# 328p_DIP_Galv_009_gnd.net
KiCad netlist of a schematic drawn in EAGLE
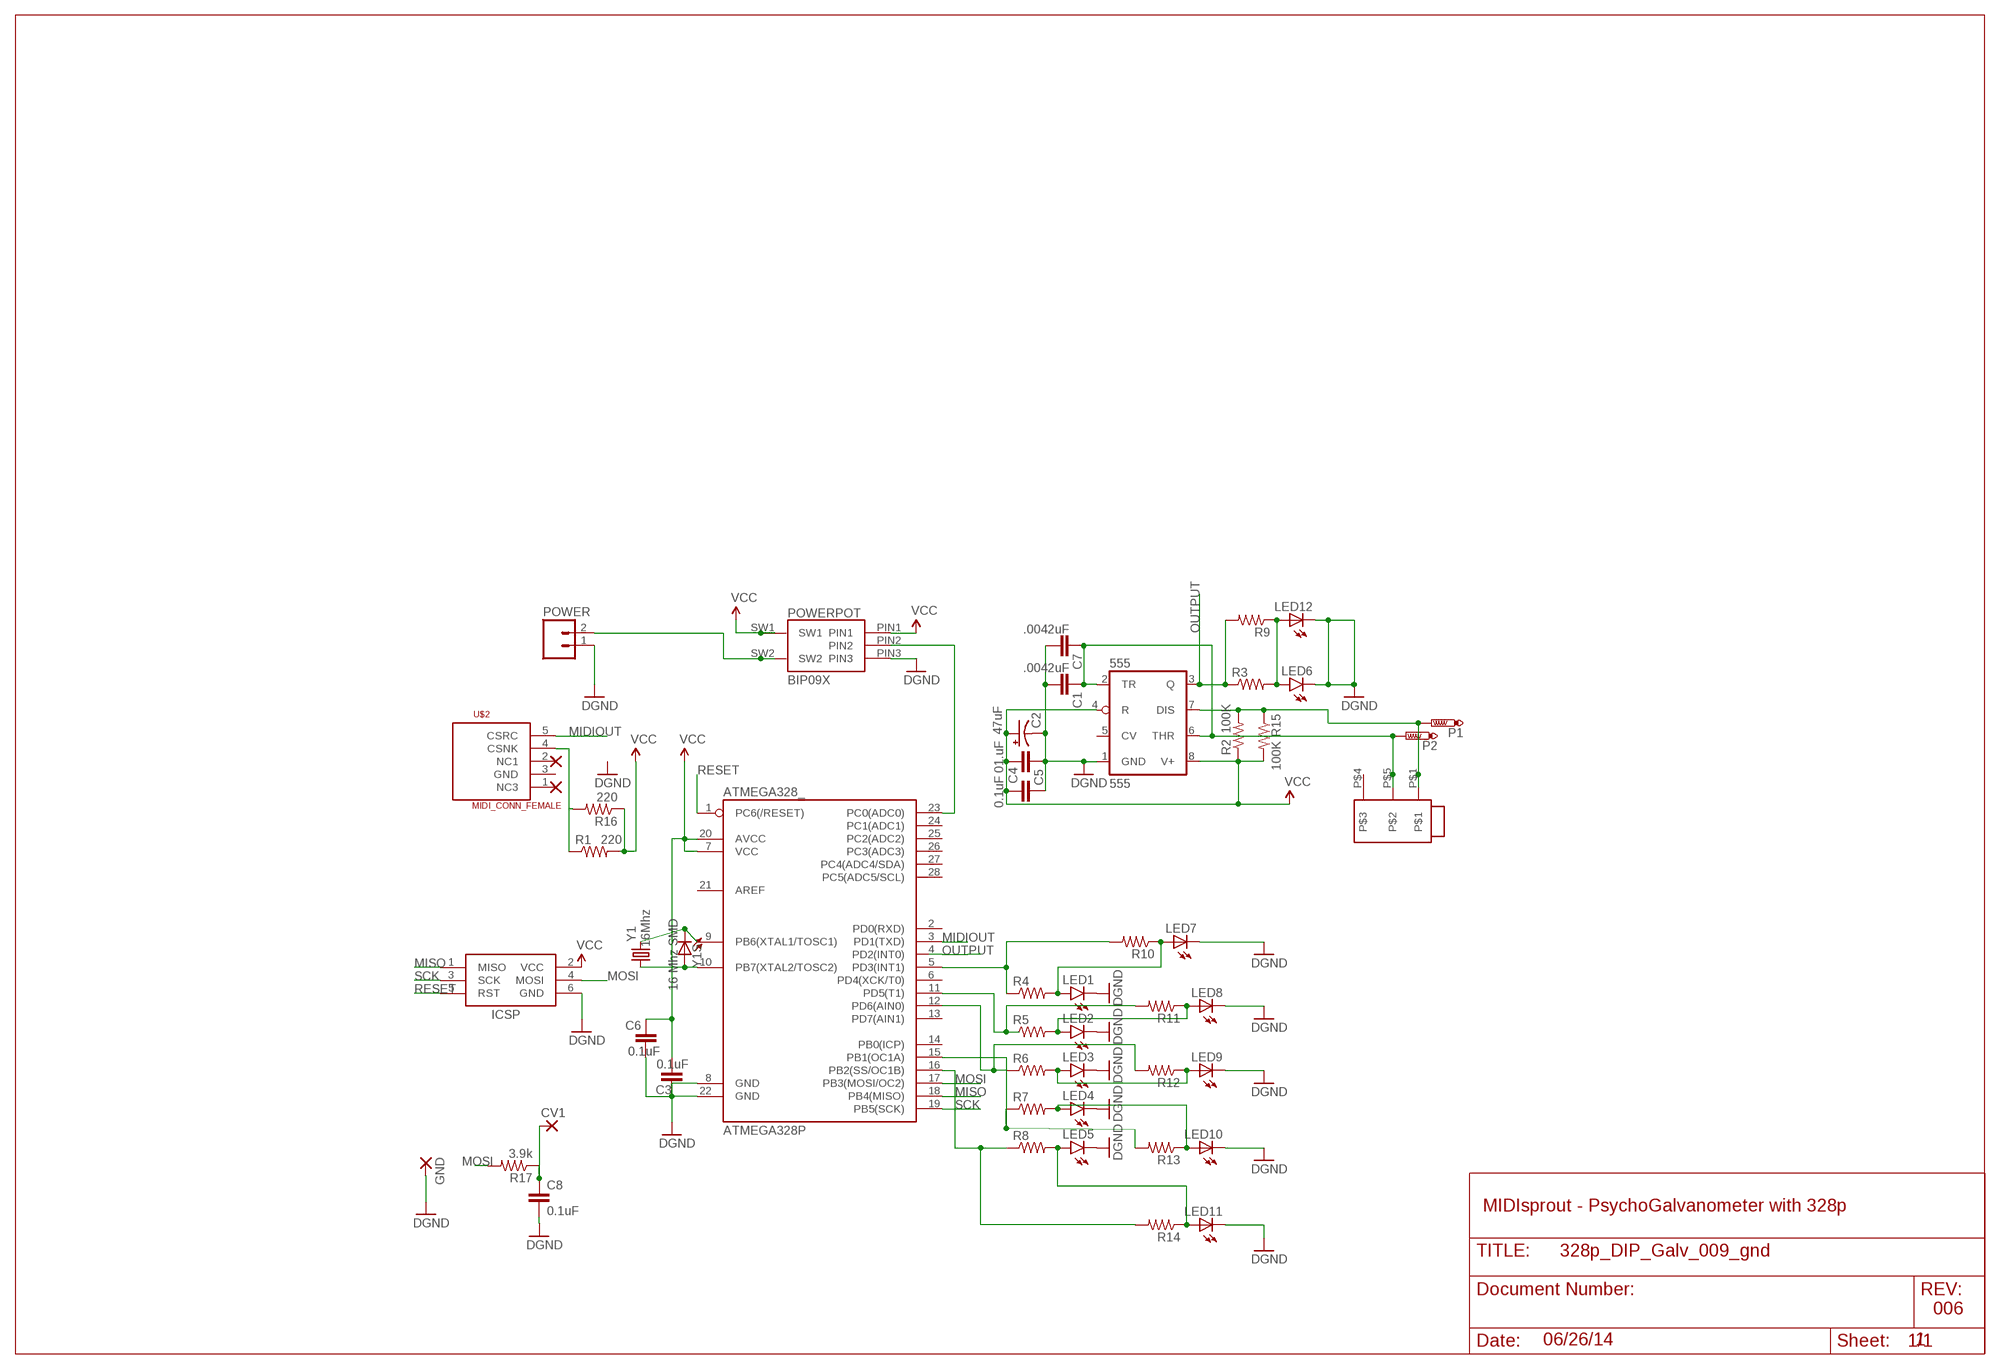
[diagram p0: schematic, sheet 1]

(export (version "E")
  (design (tool "Eeschema 10.0.6"))
  (components
    (comp (ref "555")
      (value "555")
      (footprint "eagle-import:DIL08-ROUND")
      (libsource (lib "eagle-import") (part "555NLM"))
    )
    (comp (ref "ATMEGA328_")
      (value "ATMEGA328P")
      (footprint "eagle-import:DIL28-3")
      (libsource (lib "eagle-import") (part "ATMEGA328P_PDIP"))
    )
    (comp (ref "C1")
      (value ".0042uF")
      (footprint "eagle-import:CAP-PTH-SMALL")
      (libsource (lib "eagle-import") (part "SparkFun-Passives_CAPPTH"))
    )
    (comp (ref "C2")
      (value "47uF")
      (footprint "eagle-import:CPOL-RADIAL-10UF-25V")
      (libsource (lib "eagle-import") (part "CAP_POLPTH2"))
    )
    (comp (ref "C3")
      (value "0.1uF")
      (footprint "eagle-import:CAP-PTH-SMALL")
      (libsource (lib "eagle-import") (part "CAPPTH"))
    )
    (comp (ref "C4")
      (value "0.1uF")
      (footprint "eagle-import:CAP-PTH-SMALL")
      (libsource (lib "eagle-import") (part "CAPPTH"))
    )
    (comp (ref "C5")
      (value "01.uF")
      (footprint "eagle-import:1206")
      (libsource (lib "eagle-import") (part "SparkFun-Passives_CAP1206"))
    )
    (comp (ref "C6")
      (value "0.1uF")
      (footprint "eagle-import:1206")
      (libsource (lib "eagle-import") (part "SparkFun-Passives_CAP1206"))
    )
    (comp (ref "C7")
      (value ".0042uF")
      (footprint "eagle-import:1206")
      (libsource (lib "eagle-import") (part "SparkFun-Passives_CAP1206"))
    )
    (comp (ref "C8")
      (value "0.1uF")
      (footprint "eagle-import:1206")
      (libsource (lib "eagle-import") (part "SparkFun-Passives_CAP1206"))
    )
    (comp (ref "CV1")
      (value "2,54/1,1")
      (footprint "eagle-import:2,54_1,1")
      (libsource (lib "eagle-import") (part "2,54/1,1"))
    )
    (comp (ref "GND")
      (value "2,54/1,1")
      (footprint "eagle-import:2,54_1,1")
      (libsource (lib "eagle-import") (part "2,54/1,1"))
    )
    (comp (ref "ICSP")
      (value "AVRISP-6")
      (footprint "eagle-import:AVRISP")
      (libsource (lib "eagle-import") (part "AVRISP-6"))
    )
    (comp (ref "LED1")
      (value "LED5MM")
      (footprint "eagle-import:LED5MM")
      (libsource (lib "eagle-import") (part "LED5MM"))
    )
    (comp (ref "LED2")
      (value "LED5MM")
      (footprint "eagle-import:LED5MM")
      (libsource (lib "eagle-import") (part "LED5MM"))
    )
    (comp (ref "LED3")
      (value "LED5MM")
      (footprint "eagle-import:LED5MM")
      (libsource (lib "eagle-import") (part "LED5MM"))
    )
    (comp (ref "LED4")
      (value "LED5MM")
      (footprint "eagle-import:LED5MM")
      (libsource (lib "eagle-import") (part "LED5MM"))
    )
    (comp (ref "LED5")
      (value "LED5MM")
      (footprint "eagle-import:LED5MM")
      (libsource (lib "eagle-import") (part "LED5MM"))
    )
    (comp (ref "LED6")
      (value "LED5MM")
      (footprint "eagle-import:LED5MM")
      (libsource (lib "eagle-import") (part "LED5MM"))
    )
    (comp (ref "LED7")
      (value "LEDSML1206")
      (footprint "eagle-import:SML1206")
      (libsource (lib "eagle-import") (part "LEDSML1206"))
    )
    (comp (ref "LED8")
      (value "LEDSML1206")
      (footprint "eagle-import:SML1206")
      (libsource (lib "eagle-import") (part "LEDSML1206"))
    )
    (comp (ref "LED9")
      (value "LEDSML1206")
      (footprint "eagle-import:SML1206")
      (libsource (lib "eagle-import") (part "LEDSML1206"))
    )
    (comp (ref "LED10")
      (value "LEDSML1206")
      (footprint "eagle-import:SML1206")
      (libsource (lib "eagle-import") (part "LEDSML1206"))
    )
    (comp (ref "LED11")
      (value "LEDSML1206")
      (footprint "eagle-import:SML1206")
      (libsource (lib "eagle-import") (part "LEDSML1206"))
    )
    (comp (ref "LED12")
      (value "LEDSML1206")
      (footprint "eagle-import:SML1206")
      (libsource (lib "eagle-import") (part "LEDSML1206"))
    )
    (comp (ref "P1")
      (value "PTR1PAD1-20Y")
      (footprint "eagle-import:P1-20Y")
      (libsource (lib "eagle-import") (part "PTR1PAD1-20Y"))
    )
    (comp (ref "P2")
      (value "PTR1PAD1-20Y")
      (footprint "eagle-import:P1-20Y")
      (libsource (lib "eagle-import") (part "PTR1PAD1-20Y"))
    )
    (comp (ref "POWER")
      (value "M02LOCK_LONGPADS")
      (footprint "eagle-import:1X02_LOCK_LONGPADS")
      (libsource (lib "eagle-import") (part "M02LOCK_LONGPADS"))
    )
    (comp (ref "POWERPOT")
      (value "BIP09X")
      (footprint "eagle-import:BIP09X")
      (libsource (lib "eagle-import") (part "BIP09X"))
    )
    (comp (ref "R1")
      (value "220")
      (footprint "eagle-import:AXIAL-0.3")
      (libsource (lib "eagle-import") (part "RESISTORAXIAL-0.3"))
    )
    (comp (ref "R2")
      (value "100K")
      (footprint "eagle-import:AXIAL-0.3")
      (libsource (lib "eagle-import") (part "RESISTORAXIAL-0.3"))
    )
    (comp (ref "R3")
      (value "RESISTORAXIAL-0.3")
      (footprint "eagle-import:AXIAL-0.3")
      (libsource (lib "eagle-import") (part "RESISTORAXIAL-0.3"))
    )
    (comp (ref "R4")
      (value "RESISTORAXIAL-0.3")
      (footprint "eagle-import:AXIAL-0.3")
      (libsource (lib "eagle-import") (part "RESISTORAXIAL-0.3"))
    )
    (comp (ref "R5")
      (value "RESISTORAXIAL-0.3")
      (footprint "eagle-import:AXIAL-0.3")
      (libsource (lib "eagle-import") (part "RESISTORAXIAL-0.3"))
    )
    (comp (ref "R6")
      (value "RESISTORAXIAL-0.3")
      (footprint "eagle-import:AXIAL-0.3")
      (libsource (lib "eagle-import") (part "RESISTORAXIAL-0.3"))
    )
    (comp (ref "R7")
      (value "RESISTORAXIAL-0.3")
      (footprint "eagle-import:AXIAL-0.3")
      (libsource (lib "eagle-import") (part "RESISTORAXIAL-0.3"))
    )
    (comp (ref "R8")
      (value "RESISTORAXIAL-0.3")
      (footprint "eagle-import:AXIAL-0.3")
      (libsource (lib "eagle-import") (part "RESISTORAXIAL-0.3"))
    )
    (comp (ref "R9")
      (value "R-US_R1206")
      (footprint "eagle-import:R1206")
      (libsource (lib "eagle-import") (part "R-US_R1206"))
    )
    (comp (ref "R10")
      (value "R-US_R1206")
      (footprint "eagle-import:R1206")
      (libsource (lib "eagle-import") (part "R-US_R1206"))
    )
    (comp (ref "R11")
      (value "R-US_R1206")
      (footprint "eagle-import:R1206")
      (libsource (lib "eagle-import") (part "R-US_R1206"))
    )
    (comp (ref "R12")
      (value "R-US_R1206")
      (footprint "eagle-import:R1206")
      (libsource (lib "eagle-import") (part "R-US_R1206"))
    )
    (comp (ref "R13")
      (value "R-US_R1206")
      (footprint "eagle-import:R1206")
      (libsource (lib "eagle-import") (part "R-US_R1206"))
    )
    (comp (ref "R14")
      (value "R-US_R1206")
      (footprint "eagle-import:R1206")
      (libsource (lib "eagle-import") (part "R-US_R1206"))
    )
    (comp (ref "R15")
      (value "100K")
      (footprint "eagle-import:R1206")
      (libsource (lib "eagle-import") (part "R-US_R1206"))
    )
    (comp (ref "R16")
      (value "220")
      (footprint "eagle-import:R1206")
      (libsource (lib "eagle-import") (part "R-US_R1206"))
    )
    (comp (ref "R17")
      (value "3.9k")
      (footprint "eagle-import:R1206")
      (libsource (lib "eagle-import") (part "R-US_R1206"))
    )
    (comp (ref "U$1")
      (value "MONOJACK")
      (footprint "eagle-import:MONOJACK_SWCR_3.5")
      (libsource (lib "eagle-import") (part "MONOJACK"))
    )
    (comp (ref "U$2")
      (value "MIDI_CONN_FEMALE")
      (footprint "eagle-import:DIN_5_FEMALE")
      (libsource (lib "eagle-import") (part "MIDI_CONN_FEMALE"))
    )
    (comp (ref "Y1")
      (value "16Mhz")
      (footprint "eagle-import:HC49US")
      (libsource (lib "eagle-import") (part "CRYSTALHC49US"))
    )
    (comp (ref "Y1S")
      (value "16 Mhz SMD")
      (footprint "eagle-import:SML1206")
      (libsource (lib "eagle-import") (part "LEDSML1206"))
    )
  )
  (nets
    (net (code "1") (name "/MIDIOUT") (class "Default")
      (node (ref "ATMEGA328_") (pin "3") (pinfunction "PD1(TXD)_3") (pintype "bidirectional"))
      (node (ref "U$2") (pin "5") (pinfunction "CSRC_5") (pintype "bidirectional"))
    )
    (net (code "2") (name "/MISO") (class "Default")
      (node (ref "ATMEGA328_") (pin "18") (pinfunction "PB4(MISO)_18") (pintype "bidirectional"))
      (node (ref "ICSP") (pin "1") (pinfunction "MISO_1") (pintype "input"))
    )
    (net (code "3") (name "/MOSI") (class "Default")
      (node (ref "ATMEGA328_") (pin "17") (pinfunction "PB3(MOSI/OC2)_17") (pintype "bidirectional"))
      (node (ref "ICSP") (pin "4") (pinfunction "MOSI_4") (pintype "output"))
      (node (ref "R17") (pin "2") (pinfunction "2_2") (pintype "passive"))
    )
    (net (code "4") (name "/OUTPUT") (class "Default")
      (node (ref "555") (pin "3") (pinfunction "Q_3") (pintype "output"))
      (node (ref "ATMEGA328_") (pin "4") (pinfunction "PD2(INT0)_4") (pintype "bidirectional"))
      (node (ref "R3") (pin "P$1") (pinfunction "1_P$1") (pintype "passive"))
      (node (ref "R9") (pin "2") (pinfunction "2_2") (pintype "passive"))
    )
    (net (code "5") (name "/RESET") (class "Default")
      (node (ref "ATMEGA328_") (pin "1") (pinfunction "PC6(/RESET)_1") (pintype "bidirectional"))
      (node (ref "ICSP") (pin "5") (pinfunction "RST_5") (pintype "output"))
    )
    (net (code "6") (name "/SCK") (class "Default")
      (node (ref "ATMEGA328_") (pin "19") (pinfunction "PB5(SCK)_19") (pintype "bidirectional"))
      (node (ref "ICSP") (pin "3") (pinfunction "SCK_3") (pintype "output"))
    )
    (net (code "7") (name "DGND") (class "Default")
      (node (ref "555") (pin "1") (pinfunction "GND_1") (pintype "power_in"))
      (node (ref "ATMEGA328_") (pin "22") (pinfunction "GND_22") (pintype "bidirectional"))
      (node (ref "ATMEGA328_") (pin "8") (pinfunction "GND_8") (pintype "bidirectional"))
      (node (ref "C1") (pin "2") (pinfunction "2_2") (pintype "passive"))
      (node (ref "C2") (pin "2") (pinfunction "-_2") (pintype "passive"))
      (node (ref "C3") (pin "1") (pinfunction "1_1") (pintype "passive"))
      (node (ref "C4") (pin "2") (pinfunction "2_2") (pintype "passive"))
      (node (ref "C5") (pin "1") (pinfunction "1_1") (pintype "passive"))
      (node (ref "C6") (pin "2") (pinfunction "2_2") (pintype "passive"))
      (node (ref "C7") (pin "2") (pinfunction "2_2") (pintype "passive"))
      (node (ref "C8") (pin "2") (pinfunction "2_2") (pintype "passive"))
      (node (ref "GND") (pin "1") (pinfunction "P_1") (pintype "passive"))
      (node (ref "ICSP") (pin "6") (pinfunction "GND_6") (pintype "power_in"))
      (node (ref "LED1") (pin "K") (pinfunction "C_K") (pintype "passive"))
      (node (ref "LED10") (pin "C") (pinfunction "C_C") (pintype "passive"))
      (node (ref "LED11") (pin "C") (pinfunction "C_C") (pintype "passive"))
      (node (ref "LED12") (pin "C") (pinfunction "C_C") (pintype "passive"))
      (node (ref "LED2") (pin "K") (pinfunction "C_K") (pintype "passive"))
      (node (ref "LED3") (pin "K") (pinfunction "C_K") (pintype "passive"))
      (node (ref "LED4") (pin "K") (pinfunction "C_K") (pintype "passive"))
      (node (ref "LED5") (pin "K") (pinfunction "C_K") (pintype "passive"))
      (node (ref "LED6") (pin "K") (pinfunction "C_K") (pintype "passive"))
      (node (ref "LED7") (pin "C") (pinfunction "C_C") (pintype "passive"))
      (node (ref "LED8") (pin "C") (pinfunction "C_C") (pintype "passive"))
      (node (ref "LED9") (pin "C") (pinfunction "C_C") (pintype "passive"))
      (node (ref "POWER") (pin "1") (pinfunction "1_1") (pintype "passive"))
      (node (ref "POWERPOT") (pin "PIN3") (pinfunction "PIN3_PIN3") (pintype "bidirectional"))
    )
    (net (code "8") (name "Net-(555-DIS)") (class "Default")
      (node (ref "555") (pin "7") (pinfunction "DIS_7") (pintype "input"))
      (node (ref "P1") (pin "TP") (pinfunction "TP_TP") (pintype "input"))
      (node (ref "R15") (pin "1") (pinfunction "1_1") (pintype "passive"))
      (node (ref "R2") (pin "P$2") (pinfunction "2_P$2") (pintype "passive"))
      (node (ref "U$1") (pin "P$1") (pinfunction "P$1_P$1") (pintype "bidirectional"))
    )
    (net (code "9") (name "Net-(555-THR)") (class "Default")
      (node (ref "555") (pin "2") (pinfunction "TR_2") (pintype "input"))
      (node (ref "555") (pin "6") (pinfunction "THR_6") (pintype "input"))
      (node (ref "C1") (pin "1") (pinfunction "1_1") (pintype "passive"))
      (node (ref "C7") (pin "1") (pinfunction "1_1") (pintype "passive"))
      (node (ref "P2") (pin "TP") (pinfunction "TP_TP") (pintype "input"))
      (node (ref "U$1") (pin "P$5") (pinfunction "P$2_P$5") (pintype "bidirectional"))
    )
    (net (code "10") (name "Net-(ATMEGA328_-PB1(OC1A))") (class "Default")
      (node (ref "ATMEGA328_") (pin "15") (pinfunction "PB1(OC1A)_15") (pintype "bidirectional"))
      (node (ref "R13") (pin "2") (pinfunction "2_2") (pintype "passive"))
      (node (ref "R7") (pin "P$1") (pinfunction "1_P$1") (pintype "passive"))
    )
    (net (code "11") (name "Net-(ATMEGA328_-PB2(SS{slash}OC1B))") (class "Default")
      (node (ref "ATMEGA328_") (pin "16") (pinfunction "PB2(SS/OC1B)_16") (pintype "bidirectional"))
      (node (ref "R14") (pin "2") (pinfunction "2_2") (pintype "passive"))
      (node (ref "R8") (pin "P$1") (pinfunction "1_P$1") (pintype "passive"))
    )
    (net (code "12") (name "Net-(ATMEGA328_-PB6(XTAL1{slash}TOSC1))") (class "Default")
      (node (ref "ATMEGA328_") (pin "9") (pinfunction "PB6(XTAL1/TOSC1)_9") (pintype "bidirectional"))
      (node (ref "Y1") (pin "2") (pinfunction "2_2") (pintype "passive"))
      (node (ref "Y1S") (pin "C") (pinfunction "C_C") (pintype "passive"))
    )
    (net (code "13") (name "Net-(ATMEGA328_-PB7(XTAL2{slash}TOSC2))") (class "Default")
      (node (ref "ATMEGA328_") (pin "10") (pinfunction "PB7(XTAL2/TOSC2)_10") (pintype "bidirectional"))
      (node (ref "Y1") (pin "1") (pinfunction "1_1") (pintype "passive"))
      (node (ref "Y1S") (pin "A") (pinfunction "A_A") (pintype "passive"))
    )
    (net (code "14") (name "Net-(ATMEGA328_-PC0(ADC0))") (class "Default")
      (node (ref "ATMEGA328_") (pin "23") (pinfunction "PC0(ADC0)_23") (pintype "bidirectional"))
      (node (ref "POWERPOT") (pin "PIN2") (pinfunction "PIN2_PIN2") (pintype "bidirectional"))
    )
    (net (code "15") (name "Net-(ATMEGA328_-PD3(INT1))") (class "Default")
      (node (ref "ATMEGA328_") (pin "5") (pinfunction "PD3(INT1)_5") (pintype "bidirectional"))
      (node (ref "R10") (pin "2") (pinfunction "2_2") (pintype "passive"))
      (node (ref "R4") (pin "P$1") (pinfunction "1_P$1") (pintype "passive"))
    )
    (net (code "16") (name "Net-(ATMEGA328_-PD5(T1))") (class "Default")
      (node (ref "ATMEGA328_") (pin "11") (pinfunction "PD5(T1)_11") (pintype "bidirectional"))
      (node (ref "R11") (pin "2") (pinfunction "2_2") (pintype "passive"))
      (node (ref "R5") (pin "P$1") (pinfunction "1_P$1") (pintype "passive"))
    )
    (net (code "17") (name "Net-(ATMEGA328_-PD6(AIN0))") (class "Default")
      (node (ref "ATMEGA328_") (pin "12") (pinfunction "PD6(AIN0)_12") (pintype "bidirectional"))
      (node (ref "R12") (pin "2") (pinfunction "2_2") (pintype "passive"))
      (node (ref "R6") (pin "P$1") (pinfunction "1_P$1") (pintype "passive"))
    )
    (net (code "18") (name "Net-(CV1-P)") (class "Default")
      (node (ref "C8") (pin "1") (pinfunction "1_1") (pintype "passive"))
      (node (ref "CV1") (pin "1") (pinfunction "P_1") (pintype "passive"))
      (node (ref "R17") (pin "1") (pinfunction "1_1") (pintype "passive"))
    )
    (net (code "19") (name "Net-(POWER-Pad2)") (class "Default")
      (node (ref "POWER") (pin "2") (pinfunction "2_2") (pintype "passive"))
      (node (ref "POWERPOT") (pin "SW2") (pinfunction "SW2_SW2") (pintype "bidirectional"))
    )
    (net (code "20") (name "Net-(R1-1)") (class "Default")
      (node (ref "R1") (pin "P$1") (pinfunction "1_P$1") (pintype "passive"))
      (node (ref "R16") (pin "2") (pinfunction "2_2") (pintype "passive"))
      (node (ref "U$2") (pin "4") (pinfunction "CSNK_4") (pintype "bidirectional"))
    )
    (net (code "21") (name "Net-(R3-2)") (class "Default")
      (node (ref "LED12") (pin "A") (pinfunction "A_A") (pintype "passive"))
      (node (ref "LED6") (pin "A") (pinfunction "A_A") (pintype "passive"))
      (node (ref "R3") (pin "P$2") (pinfunction "2_P$2") (pintype "passive"))
      (node (ref "R9") (pin "1") (pinfunction "1_1") (pintype "passive"))
    )
    (net (code "22") (name "Net-(R4-2)") (class "Default")
      (node (ref "LED1") (pin "A") (pinfunction "A_A") (pintype "passive"))
      (node (ref "LED7") (pin "A") (pinfunction "A_A") (pintype "passive"))
      (node (ref "R10") (pin "1") (pinfunction "1_1") (pintype "passive"))
      (node (ref "R4") (pin "P$2") (pinfunction "2_P$2") (pintype "passive"))
    )
    (net (code "23") (name "Net-(R5-2)") (class "Default")
      (node (ref "LED2") (pin "A") (pinfunction "A_A") (pintype "passive"))
      (node (ref "LED8") (pin "A") (pinfunction "A_A") (pintype "passive"))
      (node (ref "R11") (pin "1") (pinfunction "1_1") (pintype "passive"))
      (node (ref "R5") (pin "P$2") (pinfunction "2_P$2") (pintype "passive"))
    )
    (net (code "24") (name "Net-(R6-2)") (class "Default")
      (node (ref "LED3") (pin "A") (pinfunction "A_A") (pintype "passive"))
      (node (ref "LED9") (pin "A") (pinfunction "A_A") (pintype "passive"))
      (node (ref "R12") (pin "1") (pinfunction "1_1") (pintype "passive"))
      (node (ref "R6") (pin "P$2") (pinfunction "2_P$2") (pintype "passive"))
    )
    (net (code "25") (name "Net-(R7-2)") (class "Default")
      (node (ref "LED10") (pin "A") (pinfunction "A_A") (pintype "passive"))
      (node (ref "LED4") (pin "A") (pinfunction "A_A") (pintype "passive"))
      (node (ref "R13") (pin "1") (pinfunction "1_1") (pintype "passive"))
      (node (ref "R7") (pin "P$2") (pinfunction "2_P$2") (pintype "passive"))
    )
    (net (code "26") (name "Net-(R8-2)") (class "Default")
      (node (ref "LED11") (pin "A") (pinfunction "A_A") (pintype "passive"))
      (node (ref "LED5") (pin "A") (pinfunction "A_A") (pintype "passive"))
      (node (ref "R14") (pin "1") (pinfunction "1_1") (pintype "passive"))
      (node (ref "R8") (pin "P$2") (pinfunction "2_P$2") (pintype "passive"))
    )
    (net (code "27") (name "VCC") (class "Default")
      (node (ref "555") (pin "4") (pinfunction "R_4") (pintype "input"))
      (node (ref "555") (pin "8") (pinfunction "V+_8") (pintype "power_in"))
      (node (ref "ATMEGA328_") (pin "20") (pinfunction "AVCC_20") (pintype "bidirectional"))
      (node (ref "ATMEGA328_") (pin "7") (pinfunction "VCC_7") (pintype "bidirectional"))
      (node (ref "C2") (pin "1") (pinfunction "+_1") (pintype "passive"))
      (node (ref "C3") (pin "2") (pinfunction "2_2") (pintype "passive"))
      (node (ref "C4") (pin "1") (pinfunction "1_1") (pintype "passive"))
      (node (ref "C5") (pin "2") (pinfunction "2_2") (pintype "passive"))
      (node (ref "C6") (pin "1") (pinfunction "1_1") (pintype "passive"))
      (node (ref "ICSP") (pin "2") (pinfunction "VCC_2") (pintype "power_in"))
      (node (ref "POWERPOT") (pin "PIN1") (pinfunction "PIN1_PIN1") (pintype "bidirectional"))
      (node (ref "POWERPOT") (pin "SW1") (pinfunction "SW1_SW1") (pintype "bidirectional"))
      (node (ref "R1") (pin "P$2") (pinfunction "2_P$2") (pintype "passive"))
      (node (ref "R15") (pin "2") (pinfunction "2_2") (pintype "passive"))
      (node (ref "R16") (pin "1") (pinfunction "1_1") (pintype "passive"))
      (node (ref "R2") (pin "P$1") (pinfunction "1_P$1") (pintype "passive"))
    )
    (net (code "28") (name "unconnected-(555-CV-Pad5)") (class "Default")
      (node (ref "555") (pin "5") (pinfunction "CV_5") (pintype "input"))
    )
    (net (code "29") (name "unconnected-(ATMEGA328_-AREF-Pad21)") (class "Default")
      (node (ref "ATMEGA328_") (pin "21") (pinfunction "AREF_21") (pintype "bidirectional"))
    )
    (net (code "30") (name "unconnected-(ATMEGA328_-PB0(ICP)-Pad14)") (class "Default")
      (node (ref "ATMEGA328_") (pin "14") (pinfunction "PB0(ICP)_14") (pintype "bidirectional"))
    )
    (net (code "31") (name "unconnected-(ATMEGA328_-PC1(ADC1)-Pad24)") (class "Default")
      (node (ref "ATMEGA328_") (pin "24") (pinfunction "PC1(ADC1)_24") (pintype "bidirectional"))
    )
    (net (code "32") (name "unconnected-(ATMEGA328_-PC2(ADC2)-Pad25)") (class "Default")
      (node (ref "ATMEGA328_") (pin "25") (pinfunction "PC2(ADC2)_25") (pintype "bidirectional"))
    )
    (net (code "33") (name "unconnected-(ATMEGA328_-PC3(ADC3)-Pad26)") (class "Default")
      (node (ref "ATMEGA328_") (pin "26") (pinfunction "PC3(ADC3)_26") (pintype "bidirectional"))
    )
    (net (code "34") (name "unconnected-(ATMEGA328_-PC4(ADC4{slash}SDA)-Pad27)") (class "Default")
      (node (ref "ATMEGA328_") (pin "27") (pinfunction "PC4(ADC4/SDA)_27") (pintype "bidirectional"))
    )
    (net (code "35") (name "unconnected-(ATMEGA328_-PC5(ADC5{slash}SCL)-Pad28)") (class "Default")
      (node (ref "ATMEGA328_") (pin "28") (pinfunction "PC5(ADC5/SCL)_28") (pintype "bidirectional"))
    )
    (net (code "36") (name "unconnected-(ATMEGA328_-PD0(RXD)-Pad2)") (class "Default")
      (node (ref "ATMEGA328_") (pin "2") (pinfunction "PD0(RXD)_2") (pintype "bidirectional"))
    )
    (net (code "37") (name "unconnected-(ATMEGA328_-PD4(XCK{slash}T0)-Pad6)") (class "Default")
      (node (ref "ATMEGA328_") (pin "6") (pinfunction "PD4(XCK/T0)_6") (pintype "bidirectional"))
    )
    (net (code "38") (name "unconnected-(ATMEGA328_-PD7(AIN1)-Pad13)") (class "Default")
      (node (ref "ATMEGA328_") (pin "13") (pinfunction "PD7(AIN1)_13") (pintype "bidirectional"))
    )
    (net (code "39") (name "unconnected-(U$1-P$3-PadP$4)") (class "Default")
      (node (ref "U$1") (pin "P$4") (pinfunction "P$3_P$4") (pintype "bidirectional"))
    )
    (net (code "40") (name "unconnected-(U$2-GND-Pad3)") (class "Default")
      (node (ref "U$2") (pin "3") (pinfunction "GND_3") (pintype "bidirectional"))
    )
    (net (code "41") (name "unconnected-(U$2-NC1-Pad2)") (class "Default")
      (node (ref "U$2") (pin "2") (pinfunction "NC1_2") (pintype "bidirectional"))
    )
    (net (code "42") (name "unconnected-(U$2-NC3-Pad1)") (class "Default")
      (node (ref "U$2") (pin "1") (pinfunction "NC3_1") (pintype "bidirectional"))
    )
  )
)
